# smogbusters.net
KiCad netlist of a schematic drawn in EAGLE
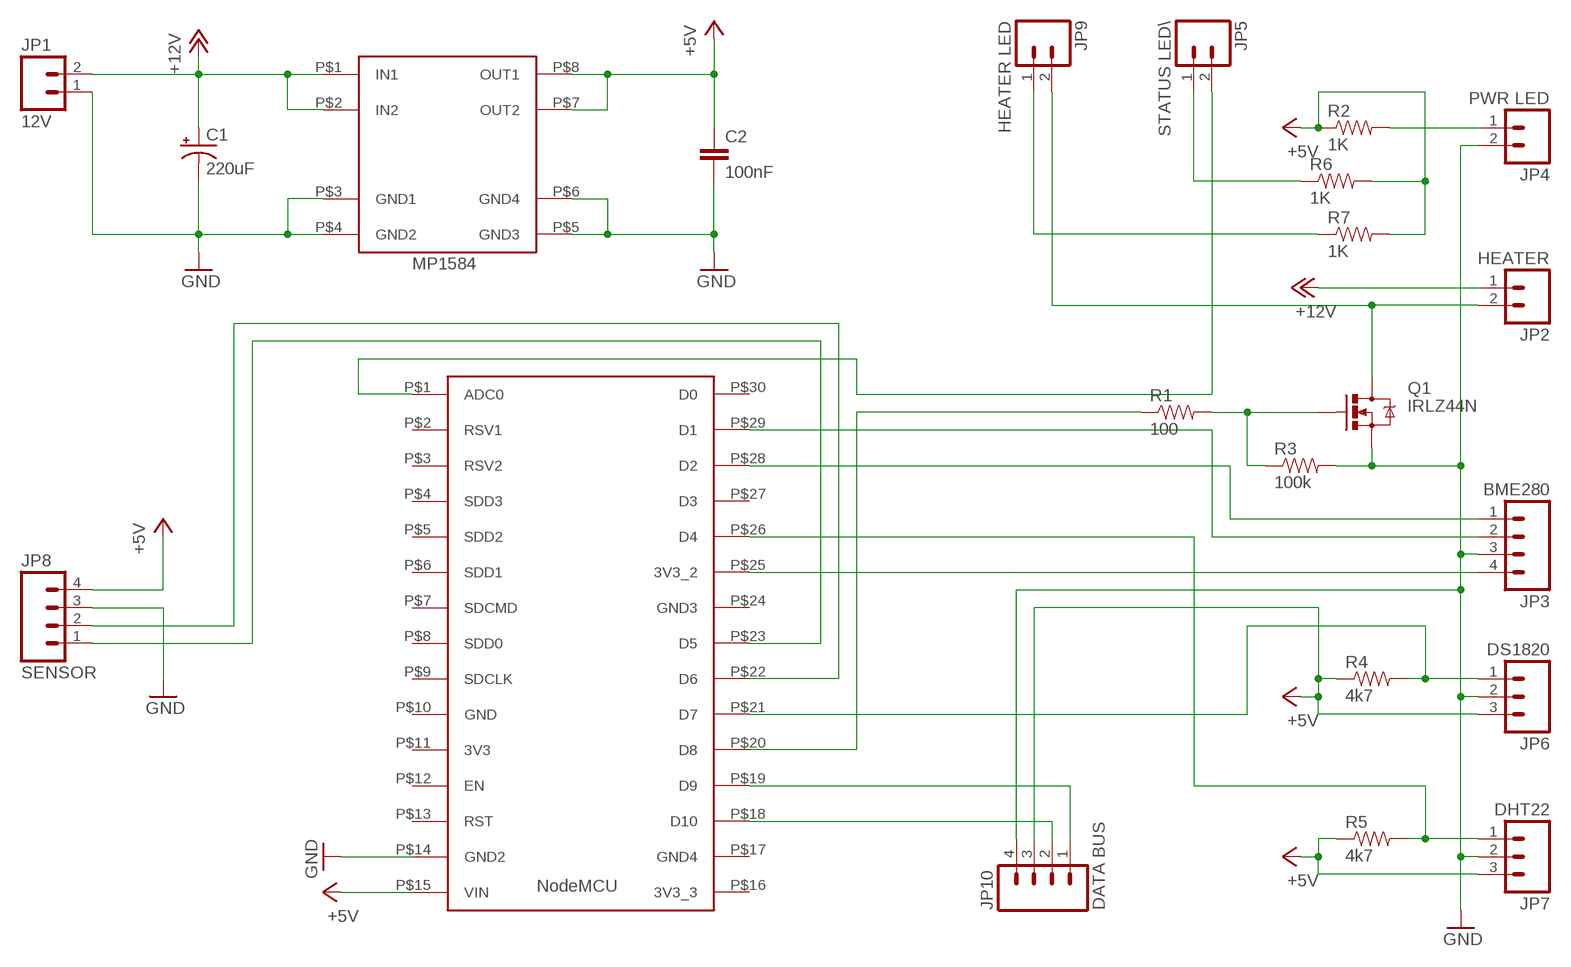
[diagram p0: schematic, sheet 1]

(export (version "E")
  (design (tool "Eeschema 10.0.6"))
  (components
    (comp (ref "C1")
      (value "220uF")
      (footprint "eagle-import:CPOL-RADIAL-100UF-25V")
      (libsource (lib "eagle-import") (part "CAP_POLPTH1"))
    )
    (comp (ref "C2")
      (value "100nF")
      (footprint "eagle-import:CAP-PTH-5MM")
      (libsource (lib "eagle-import") (part "CAPPTH1"))
    )
    (comp (ref "JP1")
      (value "12V")
      (footprint "eagle-import:SCREWTERMINAL-5MM-2")
      (libsource (lib "eagle-import") (part "M025MM"))
    )
    (comp (ref "JP2")
      (value "HEATER")
      (footprint "eagle-import:SCREWTERMINAL-5MM-2")
      (libsource (lib "eagle-import") (part "M025MM"))
    )
    (comp (ref "JP3")
      (value "BME280")
      (footprint "eagle-import:1X04")
      (libsource (lib "eagle-import") (part "M04PTH"))
    )
    (comp (ref "JP4")
      (value "PWR LED")
      (footprint "eagle-import:1X02")
      (libsource (lib "eagle-import") (part "M02PTH"))
    )
    (comp (ref "JP5")
      (value "STATUS LED\\")
      (footprint "eagle-import:1X02")
      (libsource (lib "eagle-import") (part "M02PTH"))
    )
    (comp (ref "JP6")
      (value "DS1820")
      (footprint "eagle-import:1X03")
      (libsource (lib "eagle-import") (part "M03PTH"))
    )
    (comp (ref "JP7")
      (value "DHT22")
      (footprint "eagle-import:1X03")
      (libsource (lib "eagle-import") (part "M03PTH"))
    )
    (comp (ref "JP8")
      (value "SENSOR")
      (footprint "eagle-import:MOLEX-1X4")
      (libsource (lib "eagle-import") (part "M04POLAR"))
    )
    (comp (ref "JP9")
      (value "HEATER LED")
      (footprint "eagle-import:1X02")
      (libsource (lib "eagle-import") (part "M02PTH"))
    )
    (comp (ref "JP10")
      (value "DATA BUS")
      (footprint "eagle-import:1X04")
      (libsource (lib "eagle-import") (part "M04PTH"))
    )
    (comp (ref "Q1")
      (value "IRLZ44N")
      (footprint "eagle-import:TO220V")
      (libsource (lib "eagle-import") (part "MOSFET-NCHANNELFQP30N06L"))
    )
    (comp (ref "R1")
      (value "100")
      (footprint "eagle-import:AXIAL-0.3")
      (libsource (lib "eagle-import") (part "1KOHM-1/4W-1%(PTH)"))
    )
    (comp (ref "R2")
      (value "1K")
      (footprint "eagle-import:AXIAL-0.3")
      (libsource (lib "eagle-import") (part "1KOHM-1/4W-1%(PTH)"))
    )
    (comp (ref "R3")
      (value "100k")
      (footprint "eagle-import:AXIAL-0.3")
      (libsource (lib "eagle-import") (part "1KOHM-1/4W-1%(PTH)"))
    )
    (comp (ref "R4")
      (value "4k7")
      (footprint "eagle-import:AXIAL-0.3")
      (libsource (lib "eagle-import") (part "1KOHM-1/4W-1%(PTH)"))
    )
    (comp (ref "R5")
      (value "4k7")
      (footprint "eagle-import:AXIAL-0.3")
      (libsource (lib "eagle-import") (part "1KOHM-1/4W-1%(PTH)"))
    )
    (comp (ref "R6")
      (value "1K")
      (footprint "eagle-import:AXIAL-0.3")
      (libsource (lib "eagle-import") (part "1KOHM-1/4W-1%(PTH)"))
    )
    (comp (ref "R7")
      (value "1K")
      (footprint "eagle-import:AXIAL-0.3")
      (libsource (lib "eagle-import") (part "1KOHM-1/4W-1%(PTH)"))
    )
    (comp (ref "U$1")
      (value "NODEMCU")
      (footprint "eagle-import:NODEMCU")
      (libsource (lib "eagle-import") (part "NODEMCU"))
    )
    (comp (ref "U$2")
      (value "MP1584")
      (footprint "eagle-import:MP1584")
      (libsource (lib "eagle-import") (part "MP1584"))
    )
  )
  (nets
    (net (code "1") (name "+5V") (class "Default")
      (node (ref "C2") (pin "1") (pinfunction "1_1") (pintype "passive"))
      (node (ref "JP10") (pin "3") (pinfunction "3_3") (pintype "passive"))
      (node (ref "JP6") (pin "3") (pinfunction "3_3") (pintype "passive"))
      (node (ref "JP7") (pin "3") (pinfunction "3_3") (pintype "passive"))
      (node (ref "JP8") (pin "4") (pinfunction "4_4") (pintype "passive"))
      (node (ref "R2") (pin "P$1") (pinfunction "1_P$1") (pintype "passive"))
      (node (ref "R4") (pin "P$1") (pinfunction "1_P$1") (pintype "passive"))
      (node (ref "R5") (pin "P$1") (pinfunction "1_P$1") (pintype "passive"))
      (node (ref "R6") (pin "P$2") (pinfunction "2_P$2") (pintype "passive"))
      (node (ref "R7") (pin "P$2") (pinfunction "2_P$2") (pintype "passive"))
      (node (ref "U$1") (pin "P$15") (pinfunction "VIN_P$15") (pintype "bidirectional"))
      (node (ref "U$2") (pin "P$7") (pinfunction "OUT2_P$7") (pintype "bidirectional"))
      (node (ref "U$2") (pin "P$8") (pinfunction "OUT1_P$8") (pintype "bidirectional"))
    )
    (net (code "2") (name "+12V") (class "Default")
      (node (ref "C1") (pin "1") (pinfunction "+_1") (pintype "passive"))
      (node (ref "JP1") (pin "2") (pinfunction "2_2") (pintype "passive"))
      (node (ref "JP2") (pin "1") (pinfunction "1_1") (pintype "passive"))
      (node (ref "U$2") (pin "P$1") (pinfunction "IN1_P$1") (pintype "input"))
      (node (ref "U$2") (pin "P$2") (pinfunction "IN2_P$2") (pintype "input"))
    )
    (net (code "3") (name "GND") (class "Default")
      (node (ref "C1") (pin "2") (pinfunction "-_2") (pintype "passive"))
      (node (ref "C2") (pin "2") (pinfunction "2_2") (pintype "passive"))
      (node (ref "JP1") (pin "1") (pinfunction "1_1") (pintype "passive"))
      (node (ref "JP10") (pin "4") (pinfunction "4_4") (pintype "passive"))
      (node (ref "JP3") (pin "3") (pinfunction "3_3") (pintype "passive"))
      (node (ref "JP4") (pin "2") (pinfunction "2_2") (pintype "passive"))
      (node (ref "JP6") (pin "2") (pinfunction "2_2") (pintype "passive"))
      (node (ref "JP7") (pin "2") (pinfunction "2_2") (pintype "passive"))
      (node (ref "JP8") (pin "3") (pinfunction "3_3") (pintype "passive"))
      (node (ref "Q1") (pin "3") (pinfunction "S_3") (pintype "passive"))
      (node (ref "R3") (pin "P$2") (pinfunction "2_P$2") (pintype "passive"))
      (node (ref "U$1") (pin "P$14") (pinfunction "GND2_P$14") (pintype "bidirectional"))
      (node (ref "U$2") (pin "P$3") (pinfunction "GND1_P$3") (pintype "bidirectional"))
      (node (ref "U$2") (pin "P$4") (pinfunction "GND2_P$4") (pintype "bidirectional"))
      (node (ref "U$2") (pin "P$5") (pinfunction "GND3_P$5") (pintype "bidirectional"))
      (node (ref "U$2") (pin "P$6") (pinfunction "GND4_P$6") (pintype "bidirectional"))
    )
    (net (code "4") (name "Net-(Q1-D)") (class "Default")
      (node (ref "JP2") (pin "2") (pinfunction "2_2") (pintype "passive"))
      (node (ref "JP9") (pin "2") (pinfunction "2_2") (pintype "passive"))
      (node (ref "Q1") (pin "2") (pinfunction "D_2") (pintype "passive"))
    )
    (net (code "5") (name "Net-(Q1-G)") (class "Default")
      (node (ref "Q1") (pin "1") (pinfunction "G_1") (pintype "passive"))
      (node (ref "R1") (pin "P$2") (pinfunction "2_P$2") (pintype "passive"))
      (node (ref "R3") (pin "P$1") (pinfunction "1_P$1") (pintype "passive"))
    )
    (net (code "6") (name "Net-(R1-1)") (class "Default")
      (node (ref "R1") (pin "P$1") (pinfunction "1_P$1") (pintype "passive"))
      (node (ref "U$1") (pin "P$20") (pinfunction "D8_P$20") (pintype "bidirectional"))
    )
    (net (code "7") (name "Net-(R2-2)") (class "Default")
      (node (ref "JP4") (pin "1") (pinfunction "1_1") (pintype "passive"))
      (node (ref "R2") (pin "P$2") (pinfunction "2_P$2") (pintype "passive"))
    )
    (net (code "8") (name "Net-(R4-2)") (class "Default")
      (node (ref "JP6") (pin "1") (pinfunction "1_1") (pintype "passive"))
      (node (ref "R4") (pin "P$2") (pinfunction "2_P$2") (pintype "passive"))
      (node (ref "U$1") (pin "P$21") (pinfunction "D7_P$21") (pintype "bidirectional"))
    )
    (net (code "9") (name "Net-(R5-2)") (class "Default")
      (node (ref "JP7") (pin "1") (pinfunction "1_1") (pintype "passive"))
      (node (ref "R5") (pin "P$2") (pinfunction "2_P$2") (pintype "passive"))
      (node (ref "U$1") (pin "P$26") (pinfunction "D4_P$26") (pintype "bidirectional"))
    )
    (net (code "10") (name "Net-(R6-1)") (class "Default")
      (node (ref "JP5") (pin "1") (pinfunction "1_1") (pintype "passive"))
      (node (ref "R6") (pin "P$1") (pinfunction "1_P$1") (pintype "passive"))
    )
    (net (code "11") (name "Net-(R7-1)") (class "Default")
      (node (ref "JP9") (pin "1") (pinfunction "1_1") (pintype "passive"))
      (node (ref "R7") (pin "P$1") (pinfunction "1_P$1") (pintype "passive"))
    )
    (net (code "12") (name "Net-(U$1-3V3_2)") (class "Default")
      (node (ref "JP3") (pin "4") (pinfunction "4_4") (pintype "passive"))
      (node (ref "U$1") (pin "P$25") (pinfunction "3V3_2_P$25") (pintype "bidirectional"))
    )
    (net (code "13") (name "Net-(U$1-ADC0)") (class "Default")
      (node (ref "JP5") (pin "2") (pinfunction "2_2") (pintype "passive"))
      (node (ref "U$1") (pin "P$1") (pinfunction "ADC0_P$1") (pintype "bidirectional"))
    )
    (net (code "14") (name "Net-(U$1-D1)") (class "Default")
      (node (ref "JP3") (pin "2") (pinfunction "2_2") (pintype "passive"))
      (node (ref "U$1") (pin "P$29") (pinfunction "D1_P$29") (pintype "bidirectional"))
    )
    (net (code "15") (name "Net-(U$1-D2)") (class "Default")
      (node (ref "JP3") (pin "1") (pinfunction "1_1") (pintype "passive"))
      (node (ref "U$1") (pin "P$28") (pinfunction "D2_P$28") (pintype "bidirectional"))
    )
    (net (code "16") (name "Net-(U$1-D5)") (class "Default")
      (node (ref "JP8") (pin "1") (pinfunction "1_1") (pintype "passive"))
      (node (ref "U$1") (pin "P$23") (pinfunction "D5_P$23") (pintype "bidirectional"))
    )
    (net (code "17") (name "Net-(U$1-D6)") (class "Default")
      (node (ref "JP8") (pin "2") (pinfunction "2_2") (pintype "passive"))
      (node (ref "U$1") (pin "P$22") (pinfunction "D6_P$22") (pintype "bidirectional"))
    )
    (net (code "18") (name "Net-(U$1-D9)") (class "Default")
      (node (ref "JP10") (pin "1") (pinfunction "1_1") (pintype "passive"))
      (node (ref "U$1") (pin "P$19") (pinfunction "D9_P$19") (pintype "bidirectional"))
    )
    (net (code "19") (name "Net-(U$1-D10)") (class "Default")
      (node (ref "JP10") (pin "2") (pinfunction "2_2") (pintype "passive"))
      (node (ref "U$1") (pin "P$18") (pinfunction "D10_P$18") (pintype "bidirectional"))
    )
    (net (code "20") (name "unconnected-(U$1-3V3-PadP$11)") (class "Default")
      (node (ref "U$1") (pin "P$11") (pinfunction "3V3_P$11") (pintype "bidirectional"))
    )
    (net (code "21") (name "unconnected-(U$1-3V3_3-PadP$16)") (class "Default")
      (node (ref "U$1") (pin "P$16") (pinfunction "3V3_3_P$16") (pintype "bidirectional"))
    )
    (net (code "22") (name "unconnected-(U$1-D0-PadP$30)") (class "Default")
      (node (ref "U$1") (pin "P$30") (pinfunction "D0_P$30") (pintype "bidirectional"))
    )
    (net (code "23") (name "unconnected-(U$1-D3-PadP$27)") (class "Default")
      (node (ref "U$1") (pin "P$27") (pinfunction "D3_P$27") (pintype "bidirectional"))
    )
    (net (code "24") (name "unconnected-(U$1-EN-PadP$12)") (class "Default")
      (node (ref "U$1") (pin "P$12") (pinfunction "EN_P$12") (pintype "bidirectional"))
    )
    (net (code "25") (name "unconnected-(U$1-GND-PadP$10)") (class "Default")
      (node (ref "U$1") (pin "P$10") (pinfunction "GND_P$10") (pintype "bidirectional"))
    )
    (net (code "26") (name "unconnected-(U$1-GND3-PadP$24)") (class "Default")
      (node (ref "U$1") (pin "P$24") (pinfunction "GND3_P$24") (pintype "bidirectional"))
    )
    (net (code "27") (name "unconnected-(U$1-GND4-PadP$17)") (class "Default")
      (node (ref "U$1") (pin "P$17") (pinfunction "GND4_P$17") (pintype "bidirectional"))
    )
    (net (code "28") (name "unconnected-(U$1-RST-PadP$13)") (class "Default")
      (node (ref "U$1") (pin "P$13") (pinfunction "RST_P$13") (pintype "bidirectional"))
    )
    (net (code "29") (name "unconnected-(U$1-RSV1-PadP$2)") (class "Default")
      (node (ref "U$1") (pin "P$2") (pinfunction "RSV1_P$2") (pintype "bidirectional"))
    )
    (net (code "30") (name "unconnected-(U$1-RSV2-PadP$3)") (class "Default")
      (node (ref "U$1") (pin "P$3") (pinfunction "RSV2_P$3") (pintype "bidirectional"))
    )
    (net (code "31") (name "unconnected-(U$1-SDCLK-PadP$9)") (class "Default")
      (node (ref "U$1") (pin "P$9") (pinfunction "SDCLK_P$9") (pintype "bidirectional"))
    )
    (net (code "32") (name "unconnected-(U$1-SDCMD-PadP$7)") (class "Default")
      (node (ref "U$1") (pin "P$7") (pinfunction "SDCMD_P$7") (pintype "bidirectional"))
    )
    (net (code "33") (name "unconnected-(U$1-SDD0-PadP$8)") (class "Default")
      (node (ref "U$1") (pin "P$8") (pinfunction "SDD0_P$8") (pintype "bidirectional"))
    )
    (net (code "34") (name "unconnected-(U$1-SDD1-PadP$6)") (class "Default")
      (node (ref "U$1") (pin "P$6") (pinfunction "SDD1_P$6") (pintype "bidirectional"))
    )
    (net (code "35") (name "unconnected-(U$1-SDD2-PadP$5)") (class "Default")
      (node (ref "U$1") (pin "P$5") (pinfunction "SDD2_P$5") (pintype "bidirectional"))
    )
    (net (code "36") (name "unconnected-(U$1-SDD3-PadP$4)") (class "Default")
      (node (ref "U$1") (pin "P$4") (pinfunction "SDD3_P$4") (pintype "bidirectional"))
    )
  )
)
